# Headphone-Amplifier-ClassAB-alt2.net
KiCad netlist of a schematic drawn in EAGLE
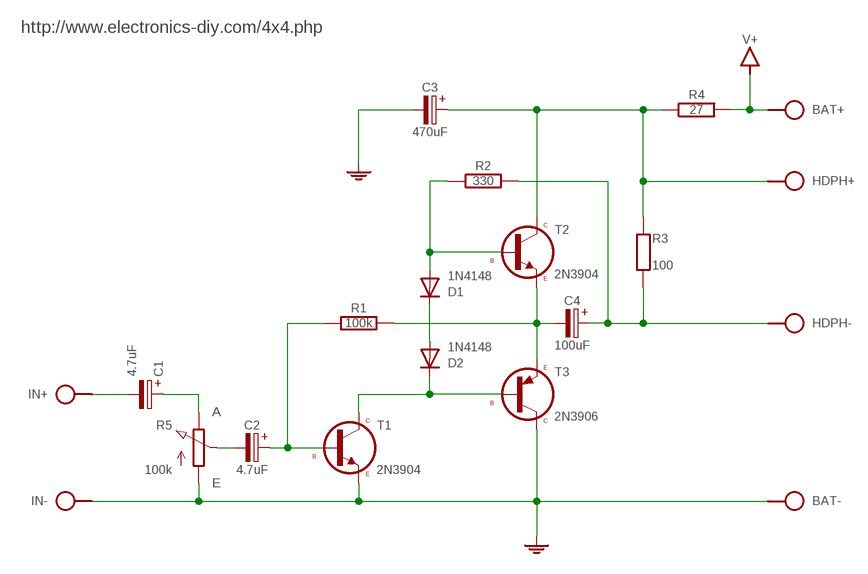
[diagram p0: schematic, sheet 1]

(export (version "E")
  (design (tool "Eeschema 10.0.6"))
  (components
    (comp (ref "BAT")
      (value "SPAD+-+-")
      (footprint "eagle-import:SPAD+-")
      (libsource (lib "eagle-import") (part "SPAD+-+-"))
    )
    (comp (ref "C1")
      (value "4.7uF")
      (footprint "eagle-import:E2,5-3")
      (libsource (lib "eagle-import") (part "CPOLE2,5-3"))
    )
    (comp (ref "C2")
      (value "4.7uF")
      (footprint "eagle-import:E2,5-3")
      (libsource (lib "eagle-import") (part "CPOLE2,5-3"))
    )
    (comp (ref "C3")
      (value "470uF")
      (footprint "eagle-import:E5-5")
      (libsource (lib "eagle-import") (part "CPOLE5-5"))
    )
    (comp (ref "C4")
      (value "100uF")
      (footprint "eagle-import:E2,5-5")
      (libsource (lib "eagle-import") (part "CPOLE2.5-5"))
    )
    (comp (ref "D1")
      (value "1N4148")
      (footprint "eagle-import:DO34-5-V")
      (libsource (lib "eagle-import") (part "DIODE34-5-V"))
    )
    (comp (ref "D2")
      (value "1N4148")
      (footprint "eagle-import:DO34-5V")
      (libsource (lib "eagle-import") (part "DIODE34-5V"))
    )
    (comp (ref "HDPH")
      (value "SPAD+--+")
      (footprint "eagle-import:SPAD-+")
      (libsource (lib "eagle-import") (part "SPAD+--+"))
    )
    (comp (ref "IN")
      (value "SPAD+--+")
      (footprint "eagle-import:SPAD-+")
      (libsource (lib "eagle-import") (part "SPAD+--+"))
    )
    (comp (ref "R1")
      (value "100k")
      (footprint "eagle-import:0204_10")
      (libsource (lib "eagle-import") (part "R-H0204/10"))
    )
    (comp (ref "R2")
      (value "330")
      (footprint "eagle-import:0204_10")
      (libsource (lib "eagle-import") (part "R-H0204/10"))
    )
    (comp (ref "R3")
      (value "100")
      (footprint "eagle-import:0204_10")
      (libsource (lib "eagle-import") (part "R0204/10"))
    )
    (comp (ref "R4")
      (value "27")
      (footprint "eagle-import:0204_10")
      (libsource (lib "eagle-import") (part "R-H0204/10"))
    )
    (comp (ref "R5")
      (value "100k")
      (footprint "eagle-import:CONN-3P")
      (libsource (lib "eagle-import") (part "POT-3P"))
    )
    (comp (ref "T1")
      (value "2N3904")
      (footprint "eagle-import:TO92")
      (libsource (lib "eagle-import") (part "2N3904"))
    )
    (comp (ref "T2")
      (value "2N3904")
      (footprint "eagle-import:TO92")
      (libsource (lib "eagle-import") (part "2N3904"))
    )
    (comp (ref "T3")
      (value "2N3906")
      (footprint "eagle-import:TO92")
      (libsource (lib "eagle-import") (part "2N3906"))
    )
  )
  (nets
    (net (code "1") (name "GND") (class "Default")
      (node (ref "BAT") (pin "1") (pinfunction "P$1_1") (pintype "passive"))
      (node (ref "C3") (pin "-") (pinfunction "-_-") (pintype "passive"))
      (node (ref "IN") (pin "1") (pinfunction "P$1_1") (pintype "passive"))
      (node (ref "R5") (pin "1") (pinfunction "A_1") (pintype "passive"))
      (node (ref "T1") (pin "1") (pinfunction "E_1") (pintype "passive"))
      (node (ref "T3") (pin "3") (pinfunction "C_3") (pintype "passive"))
    )
    (net (code "2") (name "Net-(D1-PadC)") (class "Default")
      (node (ref "D1") (pin "C") (pinfunction "C_C") (pintype "passive"))
      (node (ref "D2") (pin "A") (pinfunction "A_A") (pintype "passive"))
    )
    (net (code "3") (name "Net-(HDPHA-P$1)") (class "Default")
      (node (ref "C3") (pin "+") (pinfunction "+_+") (pintype "passive"))
      (node (ref "HDPH") (pin "2") (pinfunction "P$1_2") (pintype "passive"))
      (node (ref "R3") (pin "1") (pinfunction "2_1") (pintype "passive"))
      (node (ref "R4") (pin "1") (pinfunction "1_1") (pintype "passive"))
      (node (ref "T2") (pin "3") (pinfunction "C_3") (pintype "passive"))
    )
    (net (code "4") (name "Net-(HDPHB-P$1)") (class "Default")
      (node (ref "C4") (pin "+") (pinfunction "+_+") (pintype "passive"))
      (node (ref "HDPH") (pin "1") (pinfunction "P$1_1") (pintype "passive"))
      (node (ref "R2") (pin "2") (pinfunction "2_2") (pintype "passive"))
      (node (ref "R3") (pin "2") (pinfunction "1_2") (pintype "passive"))
    )
    (net (code "5") (name "Net-(INA-P$1)") (class "Default")
      (node (ref "C1") (pin "-") (pinfunction "-_-") (pintype "passive"))
      (node (ref "IN") (pin "2") (pinfunction "P$1_2") (pintype "passive"))
    )
    (net (code "6") (name "Net-(R5-E)") (class "Default")
      (node (ref "C1") (pin "+") (pinfunction "+_+") (pintype "passive"))
      (node (ref "R5") (pin "3") (pinfunction "E_3") (pintype "passive"))
    )
    (net (code "7") (name "Net-(R5-S)") (class "Default")
      (node (ref "C2") (pin "-") (pinfunction "-_-") (pintype "passive"))
      (node (ref "R5") (pin "2") (pinfunction "S_2") (pintype "passive"))
    )
    (net (code "8") (name "Net-(T1-B)") (class "Default")
      (node (ref "C2") (pin "+") (pinfunction "+_+") (pintype "passive"))
      (node (ref "R1") (pin "1") (pinfunction "1_1") (pintype "passive"))
      (node (ref "T1") (pin "2") (pinfunction "B_2") (pintype "passive"))
    )
    (net (code "9") (name "Net-(T1-C)") (class "Default")
      (node (ref "D2") (pin "C") (pinfunction "C_C") (pintype "passive"))
      (node (ref "T1") (pin "3") (pinfunction "C_3") (pintype "passive"))
      (node (ref "T3") (pin "2") (pinfunction "B_2") (pintype "passive"))
    )
    (net (code "10") (name "Net-(T2-B)") (class "Default")
      (node (ref "D1") (pin "A") (pinfunction "A_A") (pintype "passive"))
      (node (ref "R2") (pin "1") (pinfunction "1_1") (pintype "passive"))
      (node (ref "T2") (pin "2") (pinfunction "B_2") (pintype "passive"))
    )
    (net (code "11") (name "Net-(T2-E)") (class "Default")
      (node (ref "C4") (pin "-") (pinfunction "-_-") (pintype "passive"))
      (node (ref "R1") (pin "2") (pinfunction "2_2") (pintype "passive"))
      (node (ref "T2") (pin "1") (pinfunction "E_1") (pintype "passive"))
      (node (ref "T3") (pin "1") (pinfunction "E_1") (pintype "passive"))
    )
    (net (code "12") (name "V+") (class "Default")
      (node (ref "BAT") (pin "2") (pinfunction "P$1_2") (pintype "passive"))
      (node (ref "R4") (pin "2") (pinfunction "2_2") (pintype "passive"))
    )
  )
)
